# Algyan-5th-01.net
KiCad netlist of a schematic drawn in EAGLE
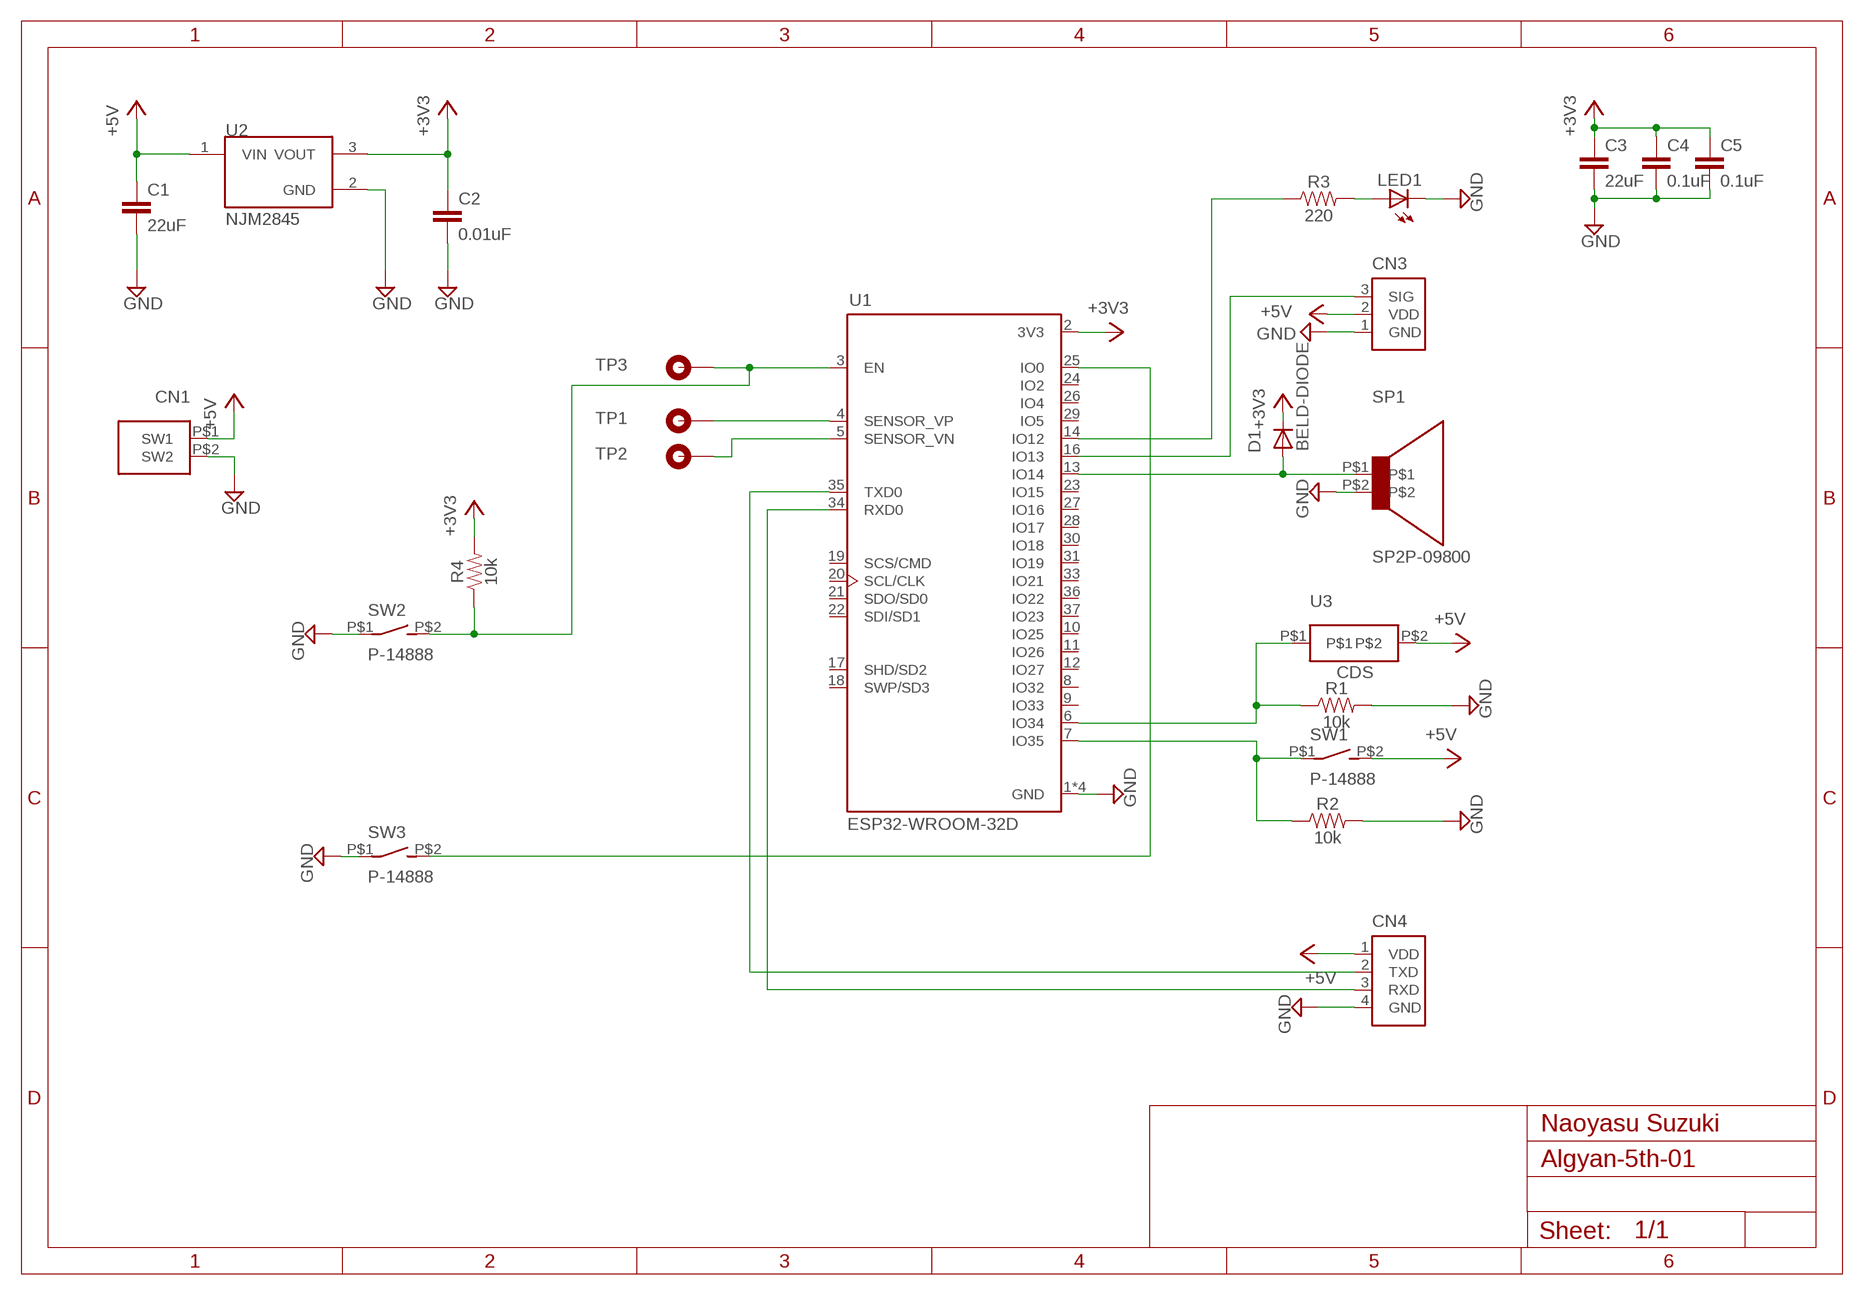
[diagram p0: schematic, sheet 1]

(export (version "E")
  (design (tool "Eeschema 10.0.6"))
  (components
    (comp (ref "C1")
      (value "22uF")
      (footprint "eagle-import:1210")
      (libsource (lib "eagle-import") (part "22UF-1210-16V-20%"))
    )
    (comp (ref "C2")
      (value "0.01uF")
      (footprint "eagle-import:0603")
      (libsource (lib "eagle-import") (part "BELD-0.01UF"))
    )
    (comp (ref "C3")
      (value "22uF")
      (footprint "eagle-import:1210")
      (libsource (lib "eagle-import") (part "22UF-1210-16V-20%"))
    )
    (comp (ref "C4")
      (value "0.1uF")
      (footprint "eagle-import:0603")
      (libsource (lib "eagle-import") (part "0.1UF-0603-25V-(+80/-20%)"))
    )
    (comp (ref "C5")
      (value "0.1uF")
      (footprint "eagle-import:0603")
      (libsource (lib "eagle-import") (part "0.1UF-0603-25V-(+80/-20%)"))
    )
    (comp (ref "CN1")
      (value "SW－WP")
      (footprint "eagle-import:SP2")
      (libsource (lib "eagle-import") (part "SW－WP"))
    )
    (comp (ref "CN3")
      (value "MIL3")
      (footprint "eagle-import:ML3")
      (libsource (lib "eagle-import") (part "MIL3"))
    )
    (comp (ref "CN4")
      (value "ESP-UART")
      (footprint "eagle-import:ML4")
      (libsource (lib "eagle-import") (part "ESP-UART"))
    )
    (comp (ref "D1")
      (value "BELD-DIODE")
      (footprint "eagle-import:DB2S40600L")
      (libsource (lib "eagle-import") (part "BELD-DIODE"))
    )
    (comp (ref "LED1")
      (value "LED3216")
      (footprint "eagle-import:3216")
      (libsource (lib "eagle-import") (part "LED3216"))
    )
    (comp (ref "R1")
      (value "10k")
      (footprint "eagle-import:0603")
      (libsource (lib "eagle-import") (part "10KOHM-0603-1/10W-1%"))
    )
    (comp (ref "R2")
      (value "10k")
      (footprint "eagle-import:0603")
      (libsource (lib "eagle-import") (part "10KOHM-0603-1/10W-1%"))
    )
    (comp (ref "R3")
      (value "220")
      (footprint "eagle-import:0603")
      (libsource (lib "eagle-import") (part "220OHM-0603-1/10W-1%"))
    )
    (comp (ref "R4")
      (value "10k")
      (footprint "eagle-import:0603")
      (libsource (lib "eagle-import") (part "10KOHM-0603-1/10W-1%"))
    )
    (comp (ref "SP1")
      (value "SP2P-09800")
      (footprint "eagle-import:P-09800")
      (libsource (lib "eagle-import") (part "SP2P-09800"))
    )
    (comp (ref "SW1")
      (value "P-14888")
      (footprint "eagle-import:P-14888")
      (libsource (lib "eagle-import") (part "P-14888"))
    )
    (comp (ref "SW2")
      (value "P-14888")
      (footprint "eagle-import:P-14888")
      (libsource (lib "eagle-import") (part "P-14888"))
    )
    (comp (ref "SW3")
      (value "P-14888")
      (footprint "eagle-import:P-14888")
      (libsource (lib "eagle-import") (part "P-14888"))
    )
    (comp (ref "TP1")
      (value "TPHOLE")
      (footprint "eagle-import:TP-HOLE")
      (libsource (lib "eagle-import") (part "TPHOLE"))
    )
    (comp (ref "TP2")
      (value "TPHOLE")
      (footprint "eagle-import:TP-HOLE")
      (libsource (lib "eagle-import") (part "TPHOLE"))
    )
    (comp (ref "TP3")
      (value "TPHOLE")
      (footprint "eagle-import:TP-HOLE")
      (libsource (lib "eagle-import") (part "TPHOLE"))
    )
    (comp (ref "U1")
      (value "ESP32-WROOM-32D")
      (footprint "eagle-import:MODULE_ESP32-WROOM-32D")
      (fields (field (name "DIGI-KEY_PART_NUMBER") "1904-1023-1-ND") (field (name "MF") "Espressif Systems"))
      (libsource (lib "eagle-import") (part "ESP32-WROOM-32D"))
    )
    (comp (ref "U2")
      (value "NJM2845")
      (footprint "eagle-import:TO252")
      (libsource (lib "eagle-import") (part "I-02247_NJM2845"))
    )
    (comp (ref "U3")
      (value "CDS")
      (footprint "eagle-import:CDS")
      (libsource (lib "eagle-import") (part "CDS"))
    )
  )
  (nets
    (net (code "1") (name "+3V3") (class "Default")
      (node (ref "C2") (pin "1") (pinfunction "1_1") (pintype "bidirectional"))
      (node (ref "C3") (pin "1") (pinfunction "1_1") (pintype "bidirectional"))
      (node (ref "C4") (pin "1") (pinfunction "1_1") (pintype "bidirectional"))
      (node (ref "C5") (pin "1") (pinfunction "1_1") (pintype "bidirectional"))
      (node (ref "D1") (pin "P$1") (pinfunction "K_P$1") (pintype "passive"))
      (node (ref "R4") (pin "2") (pinfunction "2_2") (pintype "passive"))
      (node (ref "U1") (pin "2") (pinfunction "3V3_2") (pintype "power_in"))
      (node (ref "U2") (pin "3") (pinfunction "VOUT_3") (pintype "bidirectional"))
    )
    (net (code "2") (name "+5V") (class "Default")
      (node (ref "C1") (pin "1") (pinfunction "1_1") (pintype "bidirectional"))
      (node (ref "CN1") (pin "P$1") (pinfunction "SW1_P$1") (pintype "bidirectional"))
      (node (ref "CN3") (pin "2") (pinfunction "VDD_2") (pintype "bidirectional"))
      (node (ref "CN4") (pin "1") (pinfunction "VDD_1") (pintype "bidirectional"))
      (node (ref "SW1") (pin "P$2") (pinfunction "S_P$2") (pintype "passive"))
      (node (ref "U2") (pin "1") (pinfunction "VIN_1") (pintype "bidirectional"))
      (node (ref "U3") (pin "P$2") (pinfunction "P$2_P$2") (pintype "bidirectional"))
    )
    (net (code "3") (name "GND") (class "Default")
      (node (ref "C1") (pin "2") (pinfunction "2_2") (pintype "bidirectional"))
      (node (ref "C2") (pin "2") (pinfunction "2_2") (pintype "bidirectional"))
      (node (ref "C3") (pin "2") (pinfunction "2_2") (pintype "bidirectional"))
      (node (ref "C4") (pin "2") (pinfunction "2_2") (pintype "bidirectional"))
      (node (ref "C5") (pin "2") (pinfunction "2_2") (pintype "bidirectional"))
      (node (ref "CN1") (pin "P$2") (pinfunction "SW2_P$2") (pintype "bidirectional"))
      (node (ref "CN3") (pin "1") (pinfunction "GND_1") (pintype "bidirectional"))
      (node (ref "CN4") (pin "4") (pinfunction "GND_4") (pintype "bidirectional"))
      (node (ref "LED1") (pin "P$1") (pinfunction "C_P$1") (pintype "passive"))
      (node (ref "R1") (pin "2") (pinfunction "2_2") (pintype "passive"))
      (node (ref "R2") (pin "2") (pinfunction "2_2") (pintype "passive"))
      (node (ref "SP1") (pin "P$2") (pinfunction "P$2_P$2") (pintype "bidirectional"))
      (node (ref "SW2") (pin "P$1") (pinfunction "P_P$1") (pintype "passive"))
      (node (ref "SW3") (pin "P$1") (pinfunction "P_P$1") (pintype "passive"))
      (node (ref "U1") (pin "1") (pinfunction "GND_1") (pintype "power_in"))
      (node (ref "U1") (pin "15") (pinfunction "GND_15") (pintype "power_in"))
      (node (ref "U1") (pin "38") (pinfunction "GND_38") (pintype "power_in"))
      (node (ref "U1") (pin "39") (pinfunction "GND_39") (pintype "power_in"))
      (node (ref "U2") (pin "2") (pinfunction "GND_2") (pintype "bidirectional"))
    )
    (net (code "4") (name "Net-(CN3-SIG)") (class "Default")
      (node (ref "CN3") (pin "3") (pinfunction "SIG_3") (pintype "bidirectional"))
      (node (ref "U1") (pin "16") (pinfunction "IO13_16") (pintype "bidirectional"))
    )
    (net (code "5") (name "Net-(CN4-RXD)") (class "Default")
      (node (ref "CN4") (pin "3") (pinfunction "RXD_3") (pintype "bidirectional"))
      (node (ref "U1") (pin "34") (pinfunction "RXD0_34") (pintype "bidirectional"))
    )
    (net (code "6") (name "Net-(CN4-TXD)") (class "Default")
      (node (ref "CN4") (pin "2") (pinfunction "TXD_2") (pintype "bidirectional"))
      (node (ref "U1") (pin "35") (pinfunction "TXD0_35") (pintype "bidirectional"))
    )
    (net (code "7") (name "Net-(D1-A)") (class "Default")
      (node (ref "D1") (pin "P$2") (pinfunction "A_P$2") (pintype "passive"))
      (node (ref "SP1") (pin "P$1") (pinfunction "P$1_P$1") (pintype "bidirectional"))
      (node (ref "U1") (pin "13") (pinfunction "IO14_13") (pintype "bidirectional"))
    )
    (net (code "8") (name "Net-(LED1-A)") (class "Default")
      (node (ref "LED1") (pin "P$2") (pinfunction "A_P$2") (pintype "passive"))
      (node (ref "R3") (pin "2") (pinfunction "2_2") (pintype "passive"))
    )
    (net (code "9") (name "Net-(SW1-P)") (class "Default")
      (node (ref "R2") (pin "1") (pinfunction "1_1") (pintype "passive"))
      (node (ref "SW1") (pin "P$1") (pinfunction "P_P$1") (pintype "passive"))
      (node (ref "U1") (pin "7") (pinfunction "IO35_7") (pintype "bidirectional"))
    )
    (net (code "10") (name "Net-(SW2-S)") (class "Default")
      (node (ref "R4") (pin "1") (pinfunction "1_1") (pintype "passive"))
      (node (ref "SW2") (pin "P$2") (pinfunction "S_P$2") (pintype "passive"))
      (node (ref "TP3") (pin "1") (pinfunction "1_1") (pintype "bidirectional"))
      (node (ref "U1") (pin "3") (pinfunction "EN_3") (pintype "input"))
    )
    (net (code "11") (name "Net-(SW3-S)") (class "Default")
      (node (ref "SW3") (pin "P$2") (pinfunction "S_P$2") (pintype "passive"))
      (node (ref "U1") (pin "25") (pinfunction "IO0_25") (pintype "bidirectional"))
    )
    (net (code "12") (name "Net-(U1-IO12)") (class "Default")
      (node (ref "R3") (pin "1") (pinfunction "1_1") (pintype "passive"))
      (node (ref "U1") (pin "14") (pinfunction "IO12_14") (pintype "bidirectional"))
    )
    (net (code "13") (name "Net-(U1-IO34)") (class "Default")
      (node (ref "R1") (pin "1") (pinfunction "1_1") (pintype "passive"))
      (node (ref "U1") (pin "6") (pinfunction "IO34_6") (pintype "bidirectional"))
      (node (ref "U3") (pin "P$1") (pinfunction "P$1_P$1") (pintype "bidirectional"))
    )
    (net (code "14") (name "Net-(U1-SENSOR_VN)") (class "Default")
      (node (ref "TP2") (pin "1") (pinfunction "1_1") (pintype "bidirectional"))
      (node (ref "U1") (pin "5") (pinfunction "SENSOR_VN_5") (pintype "input"))
    )
    (net (code "15") (name "Net-(U1-SENSOR_VP)") (class "Default")
      (node (ref "TP1") (pin "1") (pinfunction "1_1") (pintype "bidirectional"))
      (node (ref "U1") (pin "4") (pinfunction "SENSOR_VP_4") (pintype "input"))
    )
    (net (code "16") (name "unconnected-(U1-IO2-Pad24)") (class "Default")
      (node (ref "U1") (pin "24") (pinfunction "IO2_24") (pintype "bidirectional"))
    )
    (net (code "17") (name "unconnected-(U1-IO4-Pad26)") (class "Default")
      (node (ref "U1") (pin "26") (pinfunction "IO4_26") (pintype "bidirectional"))
    )
    (net (code "18") (name "unconnected-(U1-IO5-Pad29)") (class "Default")
      (node (ref "U1") (pin "29") (pinfunction "IO5_29") (pintype "bidirectional"))
    )
    (net (code "19") (name "unconnected-(U1-IO15-Pad23)") (class "Default")
      (node (ref "U1") (pin "23") (pinfunction "IO15_23") (pintype "bidirectional"))
    )
    (net (code "20") (name "unconnected-(U1-IO16-Pad27)") (class "Default")
      (node (ref "U1") (pin "27") (pinfunction "IO16_27") (pintype "bidirectional"))
    )
    (net (code "21") (name "unconnected-(U1-IO17-Pad28)") (class "Default")
      (node (ref "U1") (pin "28") (pinfunction "IO17_28") (pintype "bidirectional"))
    )
    (net (code "22") (name "unconnected-(U1-IO18-Pad30)") (class "Default")
      (node (ref "U1") (pin "30") (pinfunction "IO18_30") (pintype "bidirectional"))
    )
    (net (code "23") (name "unconnected-(U1-IO19-Pad31)") (class "Default")
      (node (ref "U1") (pin "31") (pinfunction "IO19_31") (pintype "bidirectional"))
    )
    (net (code "24") (name "unconnected-(U1-IO21-Pad33)") (class "Default")
      (node (ref "U1") (pin "33") (pinfunction "IO21_33") (pintype "bidirectional"))
    )
    (net (code "25") (name "unconnected-(U1-IO22-Pad36)") (class "Default")
      (node (ref "U1") (pin "36") (pinfunction "IO22_36") (pintype "bidirectional"))
    )
    (net (code "26") (name "unconnected-(U1-IO23-Pad37)") (class "Default")
      (node (ref "U1") (pin "37") (pinfunction "IO23_37") (pintype "bidirectional"))
    )
    (net (code "27") (name "unconnected-(U1-IO25-Pad10)") (class "Default")
      (node (ref "U1") (pin "10") (pinfunction "IO25_10") (pintype "bidirectional"))
    )
    (net (code "28") (name "unconnected-(U1-IO26-Pad11)") (class "Default")
      (node (ref "U1") (pin "11") (pinfunction "IO26_11") (pintype "bidirectional"))
    )
    (net (code "29") (name "unconnected-(U1-IO27-Pad12)") (class "Default")
      (node (ref "U1") (pin "12") (pinfunction "IO27_12") (pintype "bidirectional"))
    )
    (net (code "30") (name "unconnected-(U1-IO32-Pad8)") (class "Default")
      (node (ref "U1") (pin "8") (pinfunction "IO32_8") (pintype "bidirectional"))
    )
    (net (code "31") (name "unconnected-(U1-IO33-Pad9)") (class "Default")
      (node (ref "U1") (pin "9") (pinfunction "IO33_9") (pintype "bidirectional"))
    )
    (net (code "32") (name "unconnected-(U1-SCL{slash}CLK-Pad20)") (class "Default")
      (node (ref "U1") (pin "20") (pinfunction "SCL/CLK_20") (pintype "bidirectional"))
    )
    (net (code "33") (name "unconnected-(U1-SCS{slash}CMD-Pad19)") (class "Default")
      (node (ref "U1") (pin "19") (pinfunction "SCS/CMD_19") (pintype "bidirectional"))
    )
    (net (code "34") (name "unconnected-(U1-SDI{slash}SD1-Pad22)") (class "Default")
      (node (ref "U1") (pin "22") (pinfunction "SDI/SD1_22") (pintype "bidirectional"))
    )
    (net (code "35") (name "unconnected-(U1-SDO{slash}SD0-Pad21)") (class "Default")
      (node (ref "U1") (pin "21") (pinfunction "SDO/SD0_21") (pintype "bidirectional"))
    )
    (net (code "36") (name "unconnected-(U1-SHD{slash}SD2-Pad17)") (class "Default")
      (node (ref "U1") (pin "17") (pinfunction "SHD/SD2_17") (pintype "bidirectional"))
    )
    (net (code "37") (name "unconnected-(U1-SWP{slash}SD3-Pad18)") (class "Default")
      (node (ref "U1") (pin "18") (pinfunction "SWP/SD3_18") (pintype "bidirectional"))
    )
  )
)
